# Adafruit_ESP32-S2_TFT_Feather.net
KiCad netlist of a schematic drawn in EAGLE
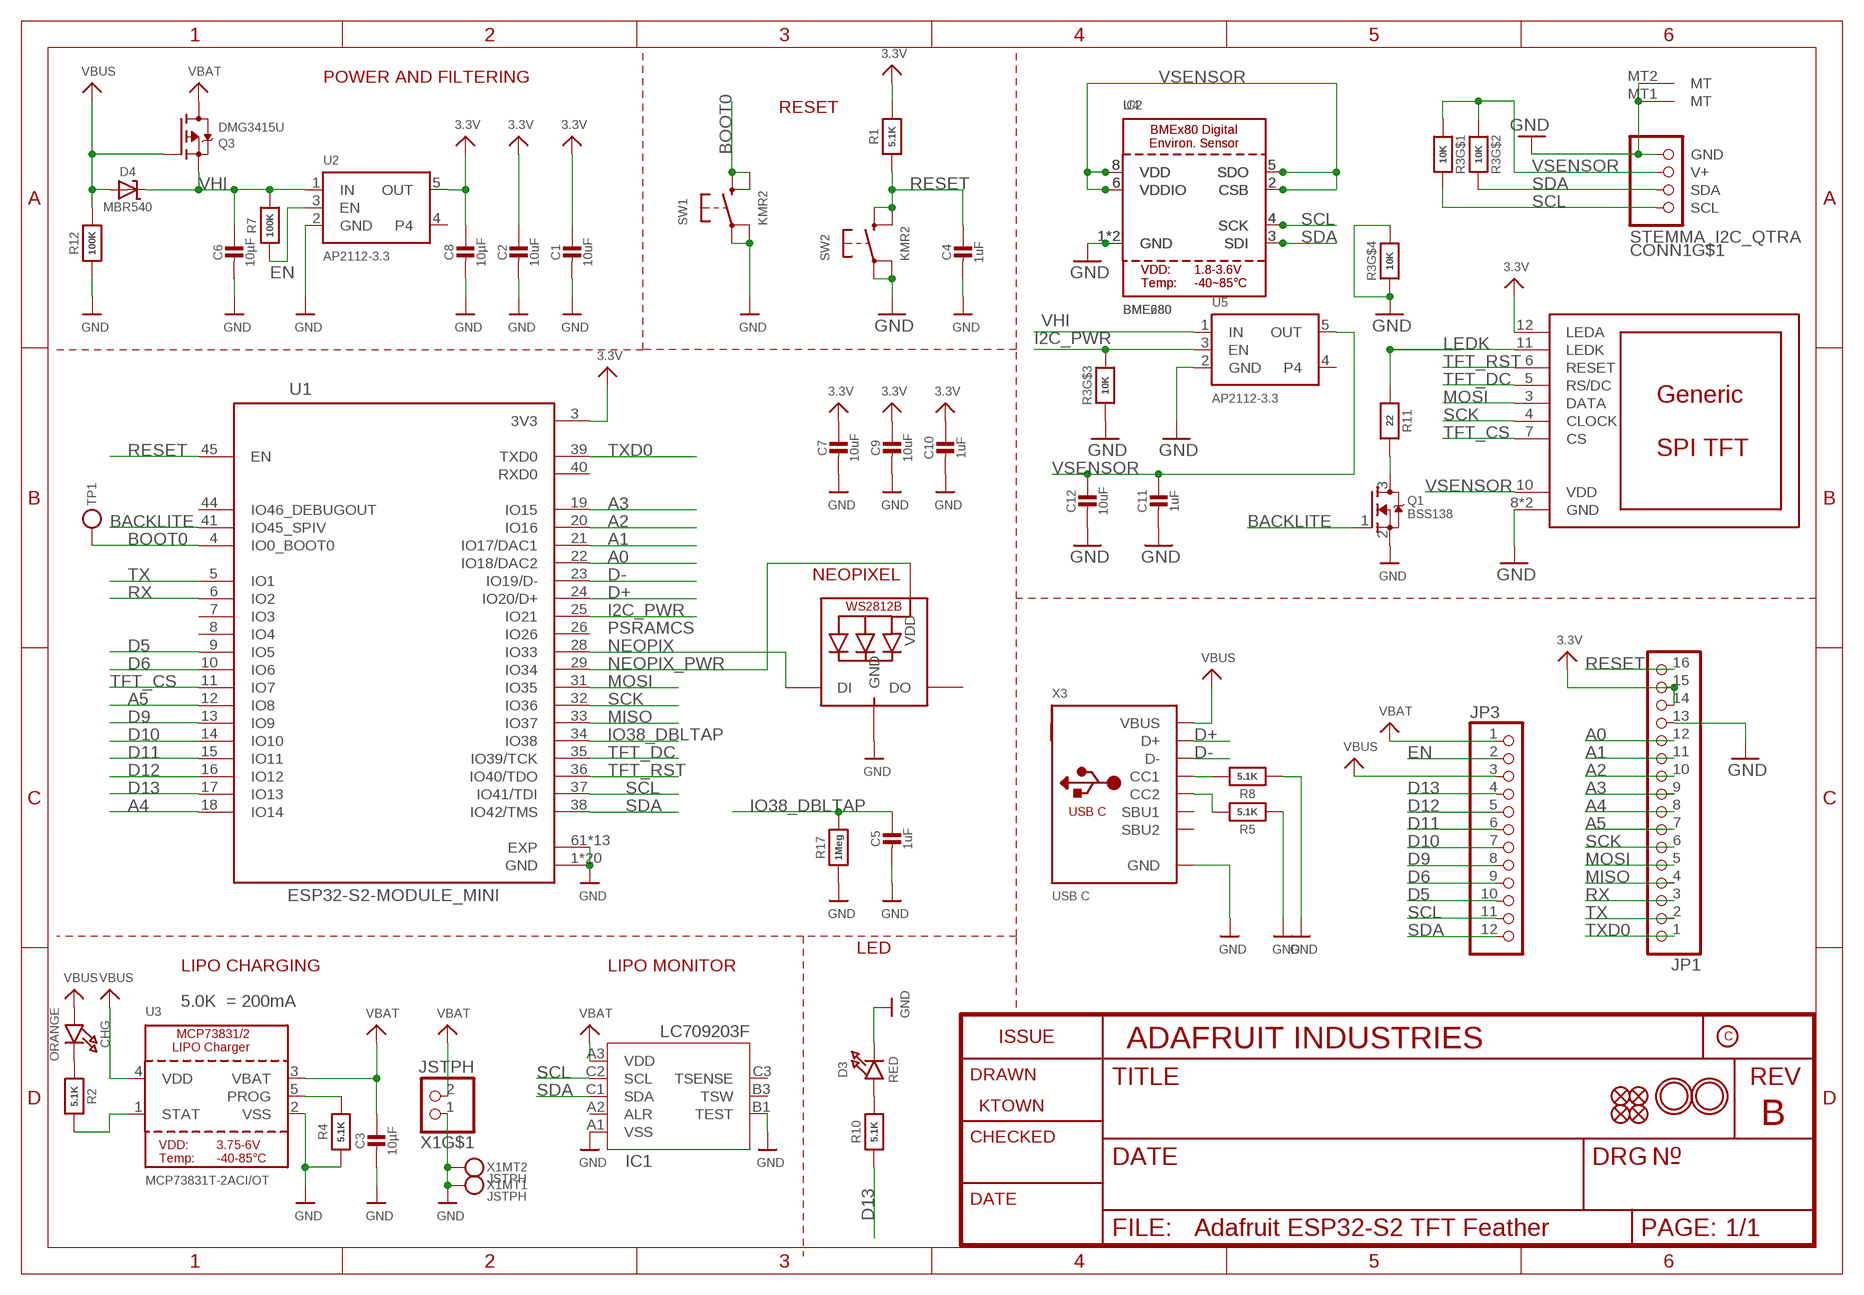
[diagram p0: schematic, sheet 1]

(export (version "E")
  (design (tool "Eeschema 10.0.6"))
  (components
    (comp (ref "C1")
      (value "10uF")
      (footprint "eagle-import:0805-NO")
      (libsource (lib "eagle-import") (part "CAP_CERAMIC0805-NOOUTLINE"))
    )
    (comp (ref "C2")
      (value "10uF")
      (footprint "eagle-import:0805-NO")
      (libsource (lib "eagle-import") (part "CAP_CERAMIC0805-NOOUTLINE"))
    )
    (comp (ref "C3")
      (value "10µF")
      (footprint "eagle-import:0805-NO")
      (libsource (lib "eagle-import") (part "CAP_CERAMIC0805-NOOUTLINE"))
    )
    (comp (ref "C4")
      (value "1uF")
      (footprint "eagle-import:0603-NO")
      (libsource (lib "eagle-import") (part "CAP_CERAMIC0603_NO"))
    )
    (comp (ref "C5")
      (value "1uF")
      (footprint "eagle-import:0603-NO")
      (libsource (lib "eagle-import") (part "CAP_CERAMIC0603_NO"))
    )
    (comp (ref "C6")
      (value "10µF")
      (footprint "eagle-import:0805-NO")
      (libsource (lib "eagle-import") (part "CAP_CERAMIC0805-NOOUTLINE"))
    )
    (comp (ref "C7")
      (value "10uF")
      (footprint "eagle-import:0805-NO")
      (libsource (lib "eagle-import") (part "CAP_CERAMIC0805-NOOUTLINE"))
    )
    (comp (ref "C8")
      (value "10µF")
      (footprint "eagle-import:0805-NO")
      (fields (field (name "REV") "C"))
      (libsource (lib "eagle-import") (part "CAP_CERAMIC0805-NOOUTLINE"))
    )
    (comp (ref "C9")
      (value "10uF")
      (footprint "eagle-import:0805-NO")
      (libsource (lib "eagle-import") (part "CAP_CERAMIC0805-NOOUTLINE"))
    )
    (comp (ref "C10")
      (value "1uF")
      (footprint "eagle-import:0603-NO")
      (libsource (lib "eagle-import") (part "CAP_CERAMIC0603_NO"))
    )
    (comp (ref "C11")
      (value "1uF")
      (footprint "eagle-import:0603-NO")
      (libsource (lib "eagle-import") (part "CAP_CERAMIC0603_NO"))
    )
    (comp (ref "C12")
      (value "10uF")
      (footprint "eagle-import:0805-NO")
      (libsource (lib "eagle-import") (part "CAP_CERAMIC0805-NOOUTLINE"))
    )
    (comp (ref "CHG")
      (value "ORANGE")
      (footprint "eagle-import:CHIPLED_0603_NOOUTLINE")
      (libsource (lib "eagle-import") (part "LED0603_NOOUTLINE"))
    )
    (comp (ref "CONN1")
      (value "STEMMA_I2C_QTRA")
      (footprint "eagle-import:JST_SH4_RA")
      (libsource (lib "eagle-import") (part "STEMMA_I2C_QTRA"))
    )
    (comp (ref "D3")
      (value "RED")
      (footprint "eagle-import:CHIPLED_0603_NOOUTLINE")
      (libsource (lib "eagle-import") (part "LED0603_NOOUTLINE"))
    )
    (comp (ref "D4")
      (value "MBR540")
      (footprint "eagle-import:SOD-123")
      (libsource (lib "eagle-import") (part "DIODE-SCHOTTKYSOD-123"))
    )
    (comp (ref "DISP1")
      (value "DISP_LCD_GENERIC_SPI_1.14IN_240X135_WRAPUNDER")
      (footprint "eagle-import:TFT_1.14IN_240X135_WRAPUNDER")
      (libsource (lib "eagle-import") (part "DISP_LCD_GENERIC_SPI_1.14IN_240X135_WRAPUNDER"))
    )
    (comp (ref "IC1")
      (value "LC709203F/MH")
      (footprint "eagle-import:WLCSP9")
      (libsource (lib "eagle-import") (part "LC709203F/MH"))
    )
    (comp (ref "IC2")
      (value "BME680")
      (footprint "eagle-import:BME680")
      (libsource (lib "eagle-import") (part "BME680"))
    )
    (comp (ref "JP1")
      (value "HEADER-1X16_MIN")
      (footprint "eagle-import:1X16_ROUND_MIN")
      (libsource (lib "eagle-import") (part "HEADER-1X16_MIN"))
    )
    (comp (ref "JP3")
      (value "HEADER-1X12_MIN")
      (footprint "eagle-import:1X12_ROUND_MIN")
      (libsource (lib "eagle-import") (part "HEADER-1X12_MIN"))
    )
    (comp (ref "LED1")
      (value "WS2812B_SK6805_1515")
      (footprint "eagle-import:SK6805_1515")
      (libsource (lib "eagle-import") (part "WS2812B_SK6805_1515"))
    )
    (comp (ref "Q1")
      (value "BSS138")
      (footprint "eagle-import:SOT23-R")
      (libsource (lib "eagle-import") (part "MOSFET-NREFLOW"))
    )
    (comp (ref "Q3")
      (value "DMG3415U")
      (footprint "eagle-import:SOT23-R")
      (libsource (lib "eagle-import") (part "MOSFET-P"))
    )
    (comp (ref "R1")
      (value "5.1K")
      (footprint "eagle-import:0603-NO")
      (libsource (lib "eagle-import") (part "RESISTOR_0603_NOOUT"))
    )
    (comp (ref "R2")
      (value "5.1K")
      (footprint "eagle-import:0603-NO")
      (libsource (lib "eagle-import") (part "RESISTOR_0603_NOOUT"))
    )
    (comp (ref "R3")
      (value "10K")
      (footprint "eagle-import:RESPACK_4X0603")
      (libsource (lib "eagle-import") (part "RESISTOR_4PACK"))
    )
    (comp (ref "R4")
      (value "5.1K")
      (footprint "eagle-import:0603-NO")
      (libsource (lib "eagle-import") (part "RESISTOR_0603_NOOUT"))
    )
    (comp (ref "R5")
      (value "5.1K")
      (footprint "eagle-import:0603-NO")
      (libsource (lib "eagle-import") (part "RESISTOR_0603_NOOUT"))
    )
    (comp (ref "R7")
      (value "100K")
      (footprint "eagle-import:0603-NO")
      (libsource (lib "eagle-import") (part "RESISTOR_0603_NOOUT"))
    )
    (comp (ref "R8")
      (value "5.1K")
      (footprint "eagle-import:0603-NO")
      (libsource (lib "eagle-import") (part "RESISTOR_0603_NOOUT"))
    )
    (comp (ref "R10")
      (value "5.1K")
      (footprint "eagle-import:0603-NO")
      (libsource (lib "eagle-import") (part "RESISTOR_0603_NOOUT"))
    )
    (comp (ref "R11")
      (value "22")
      (footprint "eagle-import:0603-NO")
      (libsource (lib "eagle-import") (part "RESISTOR_0603_NOOUT"))
    )
    (comp (ref "R12")
      (value "100K")
      (footprint "eagle-import:0603-NO")
      (libsource (lib "eagle-import") (part "RESISTOR_0603_NOOUT"))
    )
    (comp (ref "R17")
      (value "1Meg")
      (footprint "eagle-import:0603-NO")
      (libsource (lib "eagle-import") (part "RESISTOR_0603_NOOUT"))
    )
    (comp (ref "SW1")
      (value "KMR2")
      (footprint "eagle-import:BTN_KMR2_4.6X2.8")
      (libsource (lib "eagle-import") (part "SWITCH_TACT_SMT4.6X2.8"))
    )
    (comp (ref "SW2")
      (value "KMR2")
      (footprint "eagle-import:BTN_KMR2_4.6X2.8")
      (libsource (lib "eagle-import") (part "SWITCH_TACT_SMT4.6X2.8"))
    )
    (comp (ref "TP1")
      (value "TESTPOINTROUND1.5MMNO")
      (footprint "eagle-import:TESTPOINT_ROUND_1.5MM_NO")
      (libsource (lib "eagle-import") (part "TESTPOINTROUND1.5MMNO"))
    )
    (comp (ref "U$31")
      (value "MOUNTINGHOLE2.5")
      (footprint "eagle-import:MOUNTINGHOLE_2.5_PLATED")
      (libsource (lib "eagle-import") (part "MOUNTINGHOLE2.5"))
    )
    (comp (ref "U$32")
      (value "MOUNTINGHOLE2.5")
      (footprint "eagle-import:MOUNTINGHOLE_2.5_PLATED")
      (libsource (lib "eagle-import") (part "MOUNTINGHOLE2.5"))
    )
    (comp (ref "U$34")
      (value "FIDUCIAL_1MM")
      (footprint "eagle-import:FIDUCIAL_1MM")
      (libsource (lib "eagle-import") (part "FIDUCIAL_1MM"))
    )
    (comp (ref "U$35")
      (value "FIDUCIAL_1MM")
      (footprint "eagle-import:FIDUCIAL_1MM")
      (libsource (lib "eagle-import") (part "FIDUCIAL_1MM"))
    )
    (comp (ref "U$55")
      (value "FIDUCIAL_1MM")
      (footprint "eagle-import:FIDUCIAL_1MM")
      (libsource (lib "eagle-import") (part "FIDUCIAL_1MM"))
    )
    (comp (ref "U$56")
      (value "FIDUCIAL_1MM")
      (footprint "eagle-import:FIDUCIAL_1MM")
      (libsource (lib "eagle-import") (part "FIDUCIAL_1MM"))
    )
    (comp (ref "U1")
      (value "ESP32-S2-MODULE_MINI")
      (footprint "eagle-import:QFN60_ESP32-S2-MINI-1_EXP")
      (libsource (lib "eagle-import") (part "ESP32-S2-MODULE_MINI"))
    )
    (comp (ref "U2")
      (value "AP2112-3.3")
      (footprint "eagle-import:SOT23-5")
      (libsource (lib "eagle-import") (part "VREG_SOT23-5"))
    )
    (comp (ref "U3")
      (value "MCP73831T-2ACI/OT")
      (footprint "eagle-import:SOT23-5")
      (libsource (lib "eagle-import") (part "MCP73831/2"))
    )
    (comp (ref "U4")
      (value "BME280")
      (footprint "eagle-import:BME280")
      (libsource (lib "eagle-import") (part "BME280"))
    )
    (comp (ref "U5")
      (value "AP2112-3.3")
      (footprint "eagle-import:SOT23-5")
      (libsource (lib "eagle-import") (part "VREG_SOT23-5"))
    )
    (comp (ref "X1")
      (value "JSTPH")
      (footprint "eagle-import:JSTPH2_BATT")
      (libsource (lib "eagle-import") (part "CON_JST_PH_2PIN_MT_BATT"))
    )
    (comp (ref "X3")
      (value "USB C")
      (footprint "eagle-import:USB_C_CUSB31-CFM2AX-01-X")
      (libsource (lib "eagle-import") (part "USB_C"))
    )
  )
  (nets
    (net (code "1") (name "/A0") (class "Default")
      (node (ref "JP1") (pin "12") (pinfunction "12_12") (pintype "passive"))
      (node (ref "U1") (pin "22") (pinfunction "IO18/DAC2_22") (pintype "bidirectional"))
    )
    (net (code "2") (name "/A1") (class "Default")
      (node (ref "JP1") (pin "11") (pinfunction "11_11") (pintype "passive"))
      (node (ref "U1") (pin "21") (pinfunction "IO17/DAC1_21") (pintype "bidirectional"))
    )
    (net (code "3") (name "/A2") (class "Default")
      (node (ref "JP1") (pin "10") (pinfunction "10_10") (pintype "passive"))
      (node (ref "U1") (pin "20") (pinfunction "IO16_20") (pintype "bidirectional"))
    )
    (net (code "4") (name "/A3") (class "Default")
      (node (ref "JP1") (pin "9") (pinfunction "9_9") (pintype "passive"))
      (node (ref "U1") (pin "19") (pinfunction "IO15_19") (pintype "bidirectional"))
    )
    (net (code "5") (name "/A4") (class "Default")
      (node (ref "JP1") (pin "8") (pinfunction "8_8") (pintype "passive"))
      (node (ref "U1") (pin "18") (pinfunction "IO14_18") (pintype "bidirectional"))
    )
    (net (code "6") (name "/A5") (class "Default")
      (node (ref "JP1") (pin "7") (pinfunction "7_7") (pintype "passive"))
      (node (ref "U1") (pin "12") (pinfunction "IO8_12") (pintype "bidirectional"))
    )
    (net (code "7") (name "/BACKLITE") (class "Default")
      (node (ref "Q1") (pin "1") (pinfunction "G_1") (pintype "bidirectional"))
      (node (ref "U1") (pin "41") (pinfunction "IO45_SPIV_41") (pintype "bidirectional"))
    )
    (net (code "8") (name "/BOOT0") (class "Default")
      (node (ref "SW1") (pin "B") (pinfunction "S_B") (pintype "passive"))
      (node (ref "SW1") (pin "B'") (pinfunction "S1_B'") (pintype "passive"))
      (node (ref "TP1") (pin "P$1") (pinfunction "P$1_P$1") (pintype "bidirectional"))
      (node (ref "U1") (pin "4") (pinfunction "IO0_BOOT0_4") (pintype "bidirectional"))
    )
    (net (code "9") (name "/D+") (class "Default")
      (node (ref "U1") (pin "24") (pinfunction "IO20/D+_24") (pintype "bidirectional"))
      (node (ref "X3") (pin "A6") (pinfunction "D+_A6") (pintype "bidirectional"))
      (node (ref "X3") (pin "B6") (pinfunction "D+_B6") (pintype "bidirectional"))
    )
    (net (code "10") (name "/D-") (class "Default")
      (node (ref "U1") (pin "23") (pinfunction "IO19/D-_23") (pintype "bidirectional"))
      (node (ref "X3") (pin "A7") (pinfunction "D-_A7") (pintype "bidirectional"))
      (node (ref "X3") (pin "B7") (pinfunction "D-_B7") (pintype "bidirectional"))
    )
    (net (code "11") (name "/D5") (class "Default")
      (node (ref "JP3") (pin "10") (pinfunction "10_10") (pintype "passive"))
      (node (ref "U1") (pin "9") (pinfunction "IO5_9") (pintype "bidirectional"))
    )
    (net (code "12") (name "/D6") (class "Default")
      (node (ref "JP3") (pin "9") (pinfunction "9_9") (pintype "passive"))
      (node (ref "U1") (pin "10") (pinfunction "IO6_10") (pintype "bidirectional"))
    )
    (net (code "13") (name "/D9") (class "Default")
      (node (ref "JP3") (pin "8") (pinfunction "8_8") (pintype "passive"))
      (node (ref "U1") (pin "13") (pinfunction "IO9_13") (pintype "bidirectional"))
    )
    (net (code "14") (name "/D10") (class "Default")
      (node (ref "JP3") (pin "7") (pinfunction "7_7") (pintype "passive"))
      (node (ref "U1") (pin "14") (pinfunction "IO10_14") (pintype "bidirectional"))
    )
    (net (code "15") (name "/D11") (class "Default")
      (node (ref "JP3") (pin "6") (pinfunction "6_6") (pintype "passive"))
      (node (ref "U1") (pin "15") (pinfunction "IO11_15") (pintype "bidirectional"))
    )
    (net (code "16") (name "/D12") (class "Default")
      (node (ref "JP3") (pin "5") (pinfunction "5_5") (pintype "passive"))
      (node (ref "U1") (pin "16") (pinfunction "IO12_16") (pintype "bidirectional"))
    )
    (net (code "17") (name "/D13") (class "Default")
      (node (ref "JP3") (pin "4") (pinfunction "4_4") (pintype "passive"))
      (node (ref "R10") (pin "1") (pinfunction "1_1") (pintype "passive"))
      (node (ref "U1") (pin "17") (pinfunction "IO13_17") (pintype "bidirectional"))
    )
    (net (code "18") (name "/EN") (class "Default")
      (node (ref "JP3") (pin "2") (pinfunction "2_2") (pintype "passive"))
      (node (ref "R7") (pin "1") (pinfunction "1_1") (pintype "passive"))
      (node (ref "U2") (pin "3") (pinfunction "EN_3") (pintype "input"))
    )
    (net (code "19") (name "/I2C_PWR") (class "Default")
      (node (ref "R3") (pin "6") (pinfunction "2_6") (pintype "passive"))
      (node (ref "U1") (pin "25") (pinfunction "IO21_25") (pintype "bidirectional"))
      (node (ref "U5") (pin "3") (pinfunction "EN_3") (pintype "input"))
    )
    (net (code "20") (name "/IO38_DBLTAP") (class "Default")
      (node (ref "C5") (pin "1") (pinfunction "1_1") (pintype "passive"))
      (node (ref "R17") (pin "2") (pinfunction "2_2") (pintype "passive"))
      (node (ref "U1") (pin "34") (pinfunction "IO38_34") (pintype "bidirectional"))
    )
    (net (code "21") (name "/LEDK") (class "Default")
      (node (ref "DISP1") (pin "11") (pinfunction "LEDK_11") (pintype "input"))
      (node (ref "R11") (pin "1") (pinfunction "1_1") (pintype "passive"))
    )
    (net (code "22") (name "/MISO") (class "Default")
      (node (ref "JP1") (pin "4") (pinfunction "4_4") (pintype "passive"))
      (node (ref "U1") (pin "33") (pinfunction "IO37_33") (pintype "bidirectional"))
    )
    (net (code "23") (name "/MOSI") (class "Default")
      (node (ref "DISP1") (pin "3") (pinfunction "DATA_3") (pintype "bidirectional"))
      (node (ref "JP1") (pin "5") (pinfunction "5_5") (pintype "passive"))
      (node (ref "U1") (pin "31") (pinfunction "IO35_31") (pintype "input"))
    )
    (net (code "24") (name "/NEOPIX") (class "Default")
      (node (ref "LED1") (pin "1") (pinfunction "DI_1") (pintype "input"))
      (node (ref "U1") (pin "28") (pinfunction "IO33_28") (pintype "bidirectional"))
    )
    (net (code "25") (name "/NEOPIX_PWR") (class "Default")
      (node (ref "LED1") (pin "2") (pinfunction "VDD_2") (pintype "power_in"))
      (node (ref "U1") (pin "29") (pinfunction "IO34_29") (pintype "input"))
    )
    (net (code "26") (name "/RESET") (class "Default")
      (node (ref "C4") (pin "1") (pinfunction "1_1") (pintype "passive"))
      (node (ref "JP1") (pin "16") (pinfunction "16_16") (pintype "passive"))
      (node (ref "R1") (pin "1") (pinfunction "1_1") (pintype "passive"))
      (node (ref "SW2") (pin "B") (pinfunction "S_B") (pintype "passive"))
      (node (ref "SW2") (pin "B'") (pinfunction "S1_B'") (pintype "passive"))
      (node (ref "U1") (pin "45") (pinfunction "EN_45") (pintype "input"))
    )
    (net (code "27") (name "/RX") (class "Default")
      (node (ref "JP1") (pin "3") (pinfunction "3_3") (pintype "passive"))
      (node (ref "U1") (pin "6") (pinfunction "IO2_6") (pintype "bidirectional"))
    )
    (net (code "28") (name "/SCK") (class "Default")
      (node (ref "DISP1") (pin "4") (pinfunction "CLOCK_4") (pintype "input"))
      (node (ref "JP1") (pin "6") (pinfunction "6_6") (pintype "passive"))
      (node (ref "U1") (pin "32") (pinfunction "IO36_32") (pintype "bidirectional"))
    )
    (net (code "29") (name "/SCL") (class "Default")
      (node (ref "CONN1") (pin "4") (pinfunction "SCL_4") (pintype "passive"))
      (node (ref "IC1") (pin "C2") (pinfunction "SCL_C2") (pintype "bidirectional"))
      (node (ref "IC2") (pin "4") (pinfunction "SCK_4") (pintype "input"))
      (node (ref "JP3") (pin "11") (pinfunction "11_11") (pintype "passive"))
      (node (ref "R3") (pin "8") (pinfunction "2_8") (pintype "passive"))
      (node (ref "U1") (pin "37") (pinfunction "IO41/TDI_37") (pintype "bidirectional"))
      (node (ref "U4") (pin "4") (pinfunction "SCK_4") (pintype "input"))
    )
    (net (code "30") (name "/SDA") (class "Default")
      (node (ref "CONN1") (pin "3") (pinfunction "SDA_3") (pintype "passive"))
      (node (ref "IC1") (pin "C1") (pinfunction "SDA_C1") (pintype "bidirectional"))
      (node (ref "IC2") (pin "3") (pinfunction "SDI_3") (pintype "input"))
      (node (ref "JP3") (pin "12") (pinfunction "12_12") (pintype "passive"))
      (node (ref "R3") (pin "7") (pinfunction "2_7") (pintype "passive"))
      (node (ref "U1") (pin "38") (pinfunction "IO42/TMS_38") (pintype "bidirectional"))
      (node (ref "U4") (pin "3") (pinfunction "SDI_3") (pintype "input"))
    )
    (net (code "31") (name "/TFT_CS") (class "Default")
      (node (ref "DISP1") (pin "7") (pinfunction "CS_7") (pintype "input"))
      (node (ref "U1") (pin "11") (pinfunction "IO7_11") (pintype "bidirectional"))
    )
    (net (code "32") (name "/TFT_DC") (class "Default")
      (node (ref "DISP1") (pin "5") (pinfunction "RS/DC_5") (pintype "input"))
      (node (ref "U1") (pin "35") (pinfunction "IO39/TCK_35") (pintype "bidirectional"))
    )
    (net (code "33") (name "/TFT_RST") (class "Default")
      (node (ref "DISP1") (pin "6") (pinfunction "RESET_6") (pintype "input"))
      (node (ref "U1") (pin "36") (pinfunction "IO40/TDO_36") (pintype "bidirectional"))
    )
    (net (code "34") (name "/TX") (class "Default")
      (node (ref "JP1") (pin "2") (pinfunction "2_2") (pintype "passive"))
      (node (ref "U1") (pin "5") (pinfunction "IO1_5") (pintype "bidirectional"))
    )
    (net (code "35") (name "/TXD0") (class "Default")
      (node (ref "JP1") (pin "1") (pinfunction "1_1") (pintype "passive"))
      (node (ref "U1") (pin "39") (pinfunction "TXD0_39") (pintype "bidirectional"))
    )
    (net (code "36") (name "/VHI") (class "Default")
      (node (ref "C6") (pin "1") (pinfunction "1_1") (pintype "passive"))
      (node (ref "D4") (pin "C") (pinfunction "C_C") (pintype "passive"))
      (node (ref "Q3") (pin "2") (pinfunction "S_2") (pintype "passive"))
      (node (ref "R7") (pin "2") (pinfunction "2_2") (pintype "passive"))
      (node (ref "U2") (pin "1") (pinfunction "IN_1") (pintype "power_in"))
      (node (ref "U5") (pin "1") (pinfunction "IN_1") (pintype "power_in"))
    )
    (net (code "37") (name "/VSENSOR") (class "Default")
      (node (ref "C11") (pin "1") (pinfunction "1_1") (pintype "passive"))
      (node (ref "C12") (pin "1") (pinfunction "1_1") (pintype "passive"))
      (node (ref "CONN1") (pin "2") (pinfunction "V+_2") (pintype "passive"))
      (node (ref "DISP1") (pin "10") (pinfunction "VDD_10") (pintype "power_in"))
      (node (ref "IC2") (pin "2") (pinfunction "CSB_2") (pintype "input"))
      (node (ref "IC2") (pin "5") (pinfunction "SDO_5") (pintype "output"))
      (node (ref "IC2") (pin "6") (pinfunction "VDDIO_6") (pintype "power_in"))
      (node (ref "IC2") (pin "8") (pinfunction "VDD_8") (pintype "power_in"))
      (node (ref "R3") (pin "1") (pinfunction "1_1") (pintype "passive"))
      (node (ref "R3") (pin "2") (pinfunction "1_2") (pintype "passive"))
      (node (ref "U4") (pin "2") (pinfunction "CSB_2") (pintype "input"))
      (node (ref "U4") (pin "5") (pinfunction "SDO_5") (pintype "output"))
      (node (ref "U4") (pin "6") (pinfunction "VDDIO_6") (pintype "power_in"))
      (node (ref "U4") (pin "8") (pinfunction "VDD_8") (pintype "power_in"))
      (node (ref "U5") (pin "5") (pinfunction "OUT_5") (pintype "power_in"))
    )
    (net (code "38") (name "3.3V") (class "Default")
      (node (ref "C1") (pin "1") (pinfunction "1_1") (pintype "passive"))
      (node (ref "C10") (pin "1") (pinfunction "1_1") (pintype "passive"))
      (node (ref "C2") (pin "1") (pinfunction "1_1") (pintype "passive"))
      (node (ref "C7") (pin "1") (pinfunction "1_1") (pintype "passive"))
      (node (ref "C8") (pin "1") (pinfunction "1_1") (pintype "passive"))
      (node (ref "C9") (pin "1") (pinfunction "1_1") (pintype "passive"))
      (node (ref "DISP1") (pin "12") (pinfunction "LEDA_12") (pintype "input"))
      (node (ref "JP1") (pin "14") (pinfunction "14_14") (pintype "passive"))
      (node (ref "JP1") (pin "15") (pinfunction "15_15") (pintype "passive"))
      (node (ref "R1") (pin "2") (pinfunction "2_2") (pintype "passive"))
      (node (ref "U1") (pin "3") (pinfunction "3V3_3") (pintype "power_in"))
      (node (ref "U2") (pin "5") (pinfunction "OUT_5") (pintype "power_in"))
    )
    (net (code "39") (name "GND") (class "Default")
      (node (ref "C1") (pin "2") (pinfunction "2_2") (pintype "passive"))
      (node (ref "C10") (pin "2") (pinfunction "2_2") (pintype "passive"))
      (node (ref "C11") (pin "2") (pinfunction "2_2") (pintype "passive"))
      (node (ref "C12") (pin "2") (pinfunction "2_2") (pintype "passive"))
      (node (ref "C2") (pin "2") (pinfunction "2_2") (pintype "passive"))
      (node (ref "C3") (pin "2") (pinfunction "2_2") (pintype "passive"))
      (node (ref "C4") (pin "2") (pinfunction "2_2") (pintype "passive"))
      (node (ref "C5") (pin "2") (pinfunction "2_2") (pintype "passive"))
      (node (ref "C6") (pin "2") (pinfunction "2_2") (pintype "passive"))
      (node (ref "C7") (pin "2") (pinfunction "2_2") (pintype "passive"))
      (node (ref "C8") (pin "2") (pinfunction "2_2") (pintype "passive"))
      (node (ref "C9") (pin "2") (pinfunction "2_2") (pintype "passive"))
      (node (ref "CONN1") (pin "1") (pinfunction "GND_1") (pintype "passive"))
      (node (ref "CONN1") (pin "MT1") (pinfunction "MT_MT1") (pintype "bidirectional"))
      (node (ref "CONN1") (pin "MT2") (pinfunction "MT_MT2") (pintype "bidirectional"))
      (node (ref "D3") (pin "C") (pinfunction "C_C") (pintype "passive"))
      (node (ref "DISP1") (pin "13") (pinfunction "GND_13") (pintype "power_in"))
      (node (ref "DISP1") (pin "8") (pinfunction "GND_8") (pintype "power_in"))
      (node (ref "IC1") (pin "A1") (pinfunction "VSS_A1") (pintype "power_in"))
      (node (ref "IC1") (pin "B1") (pinfunction "TEST_B1") (pintype "input"))
      (node (ref "IC2") (pin "1") (pinfunction "GND_1") (pintype "power_in"))
      (node (ref "IC2") (pin "7") (pinfunction "GND_7") (pintype "power_in"))
      (node (ref "JP1") (pin "13") (pinfunction "13_13") (pintype "passive"))
      (node (ref "LED1") (pin "4") (pinfunction "GND_4") (pintype "power_in"))
      (node (ref "Q1") (pin "2") (pinfunction "S_2") (pintype "bidirectional"))
      (node (ref "R12") (pin "1") (pinfunction "1_1") (pintype "passive"))
      (node (ref "R17") (pin "1") (pinfunction "1_1") (pintype "passive"))
      (node (ref "R3") (pin "3") (pinfunction "1_3") (pintype "passive"))
      (node (ref "R3") (pin "4") (pinfunction "1_4") (pintype "passive"))
      (node (ref "R3") (pin "5") (pinfunction "2_5") (pintype "passive"))
      (node (ref "R4") (pin "1") (pinfunction "1_1") (pintype "passive"))
      (node (ref "R5") (pin "1") (pinfunction "1_1") (pintype "passive"))
      (node (ref "R8") (pin "1") (pinfunction "1_1") (pintype "passive"))
      (node (ref "SW1") (pin "A") (pinfunction "P_A") (pintype "passive"))
      (node (ref "SW1") (pin "A'") (pinfunction "P1_A'") (pintype "passive"))
      (node (ref "SW2") (pin "A") (pinfunction "P_A") (pintype "passive"))
      (node (ref "SW2") (pin "A'") (pinfunction "P1_A'") (pintype "passive"))
      (node (ref "U1") (pin "1") (pinfunction "GND_1") (pintype "power_in"))
      (node (ref "U1") (pin "2") (pinfunction "GND_2") (pintype "power_in"))
      (node (ref "U1") (pin "30") (pinfunction "GND_30") (pintype "power_in"))
      (node (ref "U1") (pin "42") (pinfunction "GND_42") (pintype "power_in"))
      (node (ref "U1") (pin "43") (pinfunction "GND_43") (pintype "power_in"))
      (node (ref "U1") (pin "46") (pinfunction "GND_46") (pintype "power_in"))
      (node (ref "U1") (pin "47") (pinfunction "GND_47") (pintype "power_in"))
      (node (ref "U1") (pin "48") (pinfunction "GND_48") (pintype "power_in"))
      (node (ref "U1") (pin "49") (pinfunction "GND_49") (pintype "power_in"))
      (node (ref "U1") (pin "50") (pinfunction "GND_50") (pintype "power_in"))
      (node (ref "U1") (pin "51") (pinfunction "GND_51") (pintype "power_in"))
      (node (ref "U1") (pin "52") (pinfunction "GND_52") (pintype "power_in"))
      (node (ref "U1") (pin "53") (pinfunction "GND_53") (pintype "power_in"))
      (node (ref "U1") (pin "54") (pinfunction "GND_54") (pintype "power_in"))
      (node (ref "U1") (pin "55") (pinfunction "GND_55") (pintype "power_in"))
      (node (ref "U1") (pin "56") (pinfunction "GND_56") (pintype "power_in"))
      (node (ref "U1") (pin "57") (pinfunction "GND_57") (pintype "power_in"))
      (node (ref "U1") (pin "58") (pinfunction "GND_58") (pintype "power_in"))
      (node (ref "U1") (pin "59") (pinfunction "GND_59") (pintype "power_in"))
      (node (ref "U1") (pin "60") (pinfunction "GND_60") (pintype "power_in"))
      (node (ref "U1") (pin "61") (pinfunction "EXP_61") (pintype "power_in"))
      (node (ref "U1") (pin "62") (pinfunction "EXP_62") (pintype "power_in"))
      (node (ref "U1") (pin "63") (pinfunction "EXP_63") (pintype "power_in"))
      (node (ref "U1") (pin "64") (pinfunction "EXP_64") (pintype "power_in"))
      (node (ref "U1") (pin "65") (pinfunction "EXP_65") (pintype "power_in"))
      (node (ref "U1") (pin "66") (pinfunction "EXP_66") (pintype "power_in"))
      (node (ref "U1") (pin "67") (pinfunction "EXP_67") (pintype "power_in"))
      (node (ref "U1") (pin "68") (pinfunction "EXP_68") (pintype "power_in"))
      (node (ref "U1") (pin "69") (pinfunction "EXP_69") (pintype "power_in"))
      (node (ref "U1") (pin "70") (pinfunction "EXP_70") (pintype "power_in"))
      (node (ref "U1") (pin "71") (pinfunction "EXP_71") (pintype "power_in"))
      (node (ref "U1") (pin "72") (pinfunction "EXP_72") (pintype "power_in"))
      (node (ref "U1") (pin "73") (pinfunction "EXP_73") (pintype "power_in"))
      (node (ref "U2") (pin "2") (pinfunction "GND_2") (pintype "power_in"))
      (node (ref "U3") (pin "2") (pinfunction "VSS_2") (pintype "power_in"))
      (node (ref "U4") (pin "1") (pinfunction "GND_1") (pintype "power_in"))
      (node (ref "U4") (pin "7") (pinfunction "GND_7") (pintype "power_in"))
      (node (ref "U5") (pin "2") (pinfunction "GND_2") (pintype "power_in"))
      (node (ref "X1") (pin "1") (pinfunction "1_1") (pintype "passive"))
      (node (ref "X1") (pin "NC1") (pinfunction "P$1_NC1") (pintype "bidirectional"))
      (node (ref "X1") (pin "NC2") (pinfunction "P$1_NC2") (pintype "bidirectional"))
      (node (ref "X3") (pin "A1B12") (pinfunction "GND_A1B12") (pintype "power_in"))
      (node (ref "X3") (pin "B1A12") (pinfunction "GND_B1A12") (pintype "power_in"))
    )
    (net (code "40") (name "Net-(CHG-PadC)") (class "Default")
      (node (ref "CHG") (pin "C") (pinfunction "C_C") (pintype "passive"))
      (node (ref "R2") (pin "1") (pinfunction "1_1") (pintype "passive"))
    )
    (net (code "41") (name "Net-(D3-PadA)") (class "Default")
      (node (ref "D3") (pin "A") (pinfunction "A_A") (pintype "passive"))
      (node (ref "R10") (pin "2") (pinfunction "2_2") (pintype "passive"))
    )
    (net (code "42") (name "Net-(Q1-D)") (class "Default")
      (node (ref "Q1") (pin "3") (pinfunction "D_3") (pintype "bidirectional"))
      (node (ref "R11") (pin "2") (pinfunction "2_2") (pintype "passive"))
    )
    (net (code "43") (name "Net-(U3-PROG)") (class "Default")
      (node (ref "R4") (pin "2") (pinfunction "2_2") (pintype "passive"))
      (node (ref "U3") (pin "5") (pinfunction "PROG_5") (pintype "input"))
    )
    (net (code "44") (name "Net-(U3-STAT)") (class "Default")
      (node (ref "R2") (pin "2") (pinfunction "2_2") (pintype "passive"))
      (node (ref "U3") (pin "1") (pinfunction "STAT_1") (pintype "output"))
    )
    (net (code "45") (name "Net-(X3-CC1)") (class "Default")
      (node (ref "R8") (pin "2") (pinfunction "2_2") (pintype "passive"))
      (node (ref "X3") (pin "A5") (pinfunction "CC1_A5") (pintype "bidirectional"))
    )
    (net (code "46") (name "Net-(X3-CC2)") (class "Default")
      (node (ref "R5") (pin "2") (pinfunction "2_2") (pintype "passive"))
      (node (ref "X3") (pin "B5") (pinfunction "CC2_B5") (pintype "bidirectional"))
    )
    (net (code "47") (name "VBAT") (class "Default")
      (node (ref "C3") (pin "1") (pinfunction "1_1") (pintype "passive"))
      (node (ref "IC1") (pin "A3") (pinfunction "VDD_A3") (pintype "power_in"))
      (node (ref "JP3") (pin "1") (pinfunction "1_1") (pintype "passive"))
      (node (ref "Q3") (pin "3") (pinfunction "D_3") (pintype "passive"))
      (node (ref "U3") (pin "3") (pinfunction "VBAT_3") (pintype "power_in"))
      (node (ref "X1") (pin "2") (pinfunction "2_2") (pintype "passive"))
    )
    (net (code "48") (name "VBUS") (class "Default")
      (node (ref "CHG") (pin "A") (pinfunction "A_A") (pintype "passive"))
      (node (ref "D4") (pin "A") (pinfunction "A_A") (pintype "passive"))
      (node (ref "JP3") (pin "3") (pinfunction "3_3") (pintype "passive"))
      (node (ref "Q3") (pin "1") (pinfunction "G_1") (pintype "passive"))
      (node (ref "R12") (pin "2") (pinfunction "2_2") (pintype "passive"))
      (node (ref "U3") (pin "4") (pinfunction "VDD_4") (pintype "power_in"))
      (node (ref "X3") (pin "A4B9") (pinfunction "VBUS_A4B9") (pintype "power_in"))
      (node (ref "X3") (pin "B4A9") (pinfunction "VBUS_B4A9") (pintype "power_in"))
    )
    (net (code "49") (name "unconnected-(IC1-ALR-PadA2)") (class "Default")
      (node (ref "IC1") (pin "A2") (pinfunction "ALR_A2") (pintype "output"))
    )
    (net (code "50") (name "unconnected-(IC1-TSENSE-PadC3)") (class "Default")
      (node (ref "IC1") (pin "C3") (pinfunction "TSENSE_C3") (pintype "passive"))
    )
    (net (code "51") (name "unconnected-(IC1-TSW-PadB3)") (class "Default")
      (node (ref "IC1") (pin "B3") (pinfunction "TSW_B3") (pintype "output"))
    )
    (net (code "52") (name "unconnected-(LED1-DO-Pad3)") (class "Default")
      (node (ref "LED1") (pin "3") (pinfunction "DO_3") (pintype "output"))
    )
    (net (code "53") (name "unconnected-(U1-IO3-Pad7)") (class "Default")
      (node (ref "U1") (pin "7") (pinfunction "IO3_7") (pintype "bidirectional"))
    )
    (net (code "54") (name "unconnected-(U1-IO4-Pad8)") (class "Default")
      (node (ref "U1") (pin "8") (pinfunction "IO4_8") (pintype "bidirectional"))
    )
    (net (code "55") (name "unconnected-(U1-IO26-Pad26)") (class "Default")
      (node (ref "U1") (pin "26") (pinfunction "IO26_26") (pintype "bidirectional"))
    )
    (net (code "56") (name "unconnected-(U1-IO46_DEBUGOUT-Pad44)") (class "Default")
      (node (ref "U1") (pin "44") (pinfunction "IO46_DEBUGOUT_44") (pintype "input"))
    )
    (net (code "57") (name "unconnected-(U1-RXD0-Pad40)") (class "Default")
      (node (ref "U1") (pin "40") (pinfunction "RXD0_40") (pintype "bidirectional"))
    )
    (net (code "58") (name "unconnected-(U2-P4-Pad4)") (class "Default")
      (node (ref "U2") (pin "4") (pinfunction "P4_4") (pintype "bidirectional"))
    )
    (net (code "59") (name "unconnected-(U5-P4-Pad4)") (class "Default")
      (node (ref "U5") (pin "4") (pinfunction "P4_4") (pintype "bidirectional"))
    )
    (net (code "60") (name "unconnected-(X3-SBU1-PadA8)") (class "Default")
      (node (ref "X3") (pin "A8") (pinfunction "SBU1_A8") (pintype "bidirectional"))
    )
    (net (code "61") (name "unconnected-(X3-SBU2-PadB8)") (class "Default")
      (node (ref "X3") (pin "B8") (pinfunction "SBU2_B8") (pintype "bidirectional"))
    )
  )
)
